# USB_FTDI.net
KiCad netlist of a schematic drawn in EAGLE
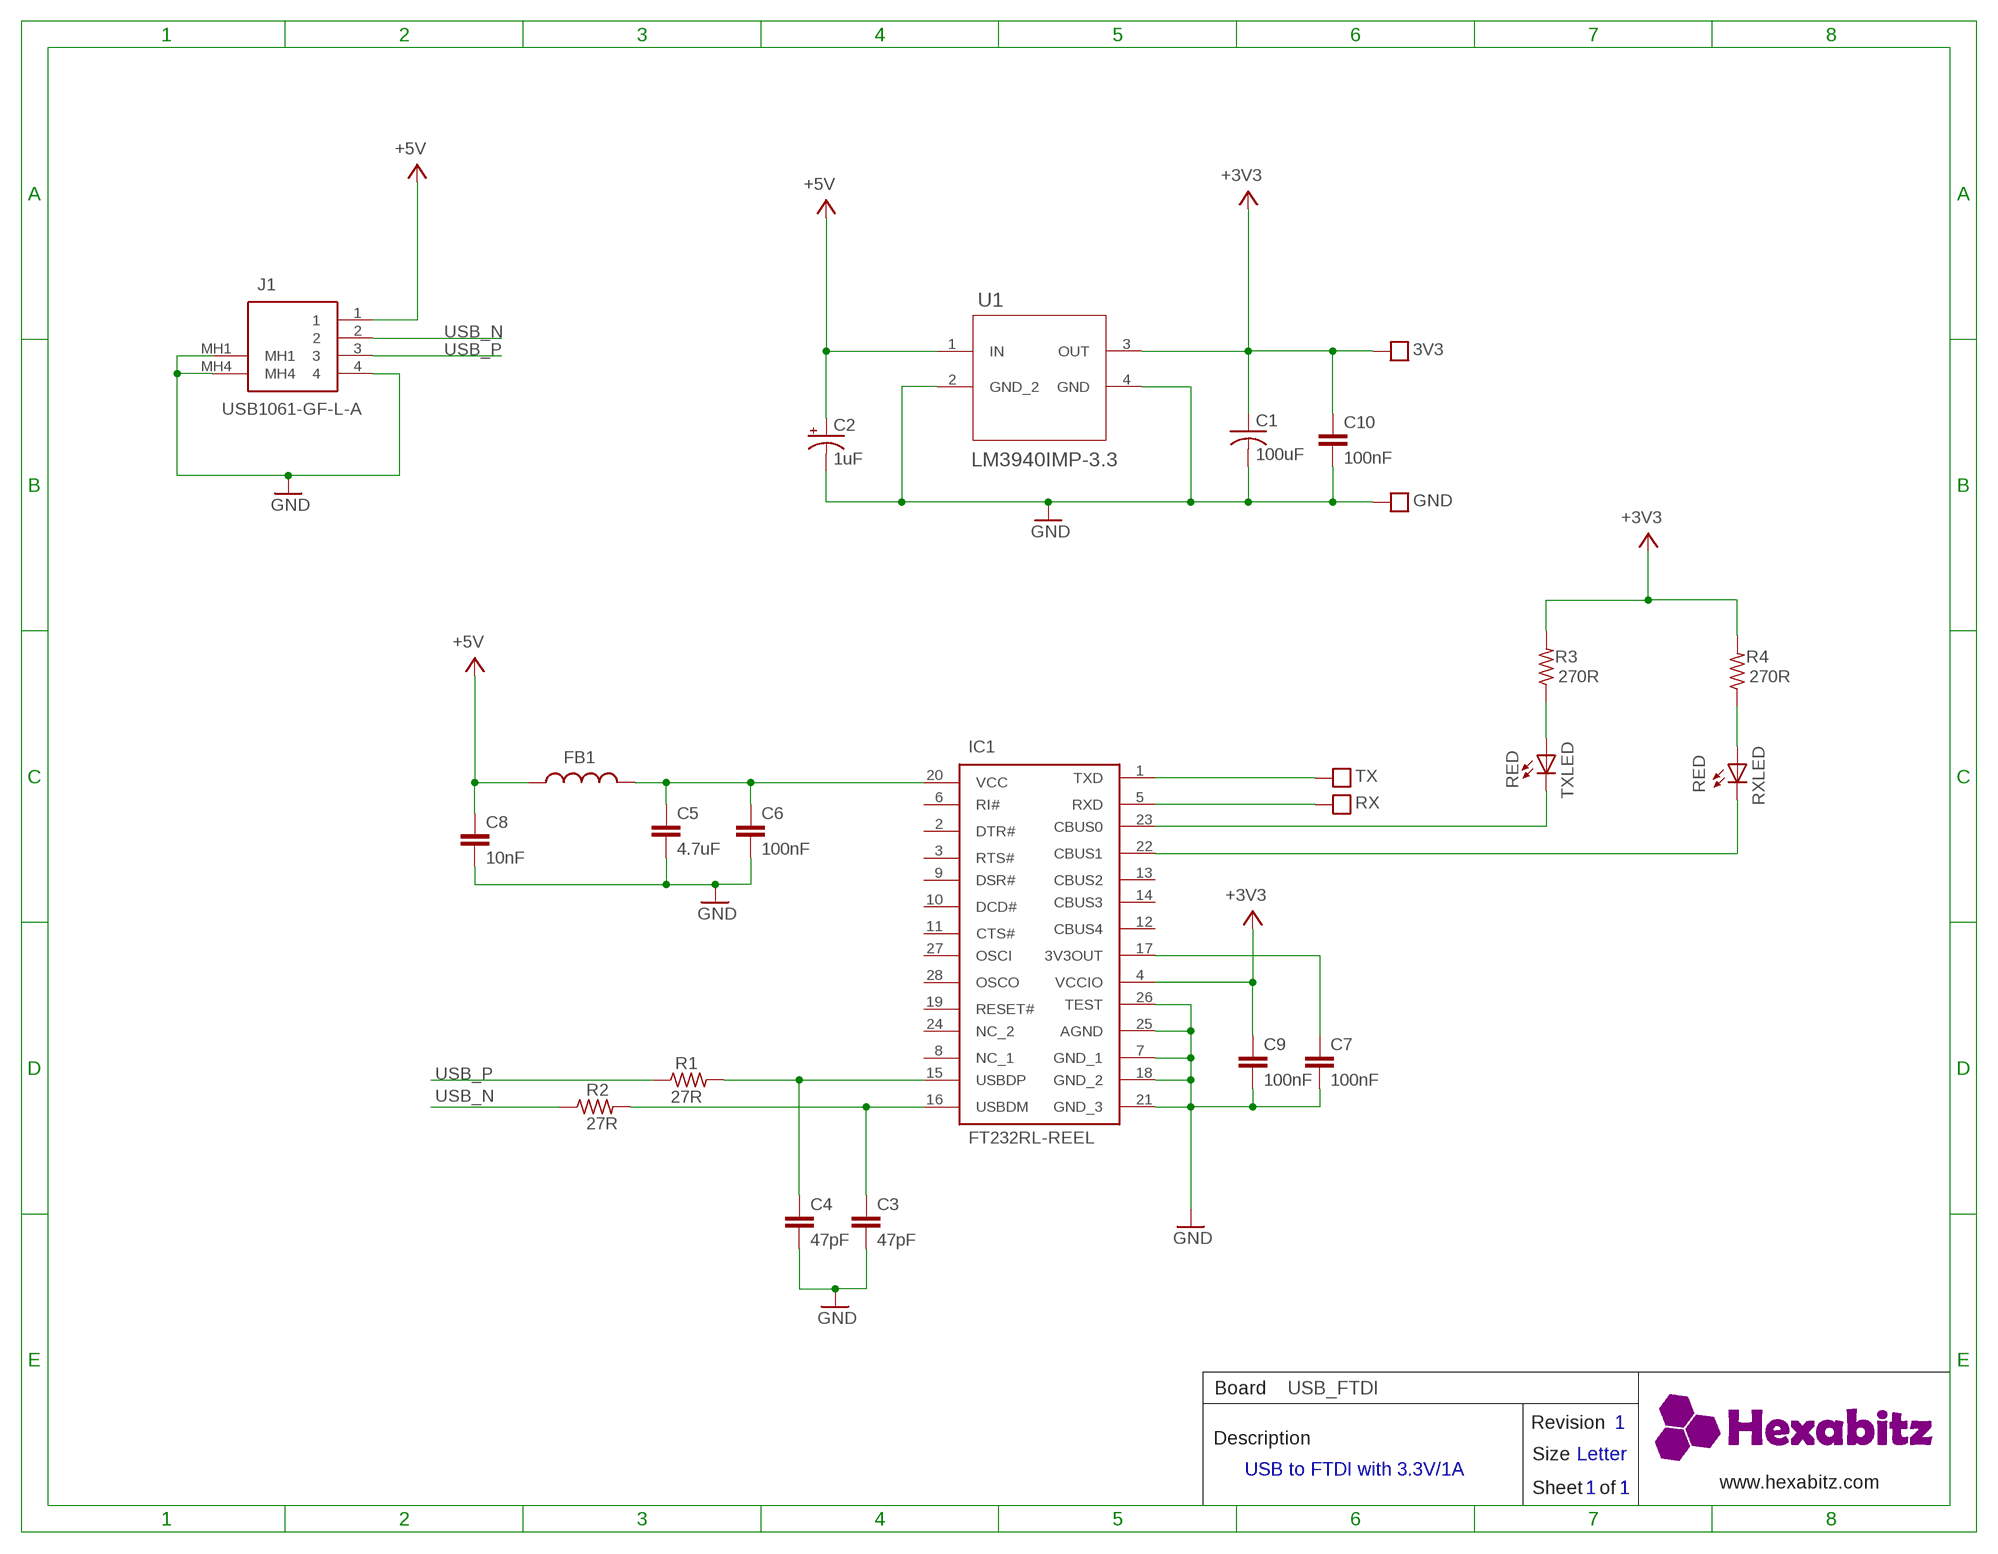
[diagram p0: schematic, sheet 1]

(export (version "E")
  (design (tool "Eeschema 10.0.6"))
  (components
    (comp (ref "3V3")
      (value "PAD5")
      (footprint "eagle-import:PAD5")
      (libsource (lib "eagle-import") (part "PAD5"))
    )
    (comp (ref "C1")
      (value "100uF")
      (footprint "eagle-import:C-1210")
      (libsource (lib "eagle-import") (part "C-1210"))
    )
    (comp (ref "C2")
      (value "1uF")
      (footprint "eagle-import:C-0805-POL")
      (libsource (lib "eagle-import") (part "C-0805-POL"))
    )
    (comp (ref "C3")
      (value "47pF")
      (footprint "eagle-import:C-0603")
      (libsource (lib "eagle-import") (part "C-0603"))
    )
    (comp (ref "C4")
      (value "47pF")
      (footprint "eagle-import:C-0603")
      (libsource (lib "eagle-import") (part "C-0603"))
    )
    (comp (ref "C5")
      (value "4.7uF")
      (footprint "eagle-import:C-0805")
      (libsource (lib "eagle-import") (part "C-0805"))
    )
    (comp (ref "C6")
      (value "100nF")
      (footprint "eagle-import:C-0603")
      (libsource (lib "eagle-import") (part "C-0603"))
    )
    (comp (ref "C7")
      (value "100nF")
      (footprint "eagle-import:C-0603")
      (libsource (lib "eagle-import") (part "C-0603"))
    )
    (comp (ref "C8")
      (value "10nF")
      (footprint "eagle-import:C-0603")
      (libsource (lib "eagle-import") (part "C-0603"))
    )
    (comp (ref "C9")
      (value "100nF")
      (footprint "eagle-import:C-0603")
      (libsource (lib "eagle-import") (part "C-0603"))
    )
    (comp (ref "C10")
      (value "100nF")
      (footprint "eagle-import:C-0603")
      (libsource (lib "eagle-import") (part "C-0603"))
    )
    (comp (ref "FB1")
      (value "FB-0603")
      (footprint "eagle-import:FB-0603")
      (libsource (lib "eagle-import") (part "FB-0603"))
    )
    (comp (ref "GND")
      (value "PAD5")
      (footprint "eagle-import:PAD5")
      (libsource (lib "eagle-import") (part "PAD5"))
    )
    (comp (ref "IC1")
      (value "FT232RL-REEL")
      (footprint "eagle-import:SOP65P778X200-28N")
      (fields (field (name "MOUSER_PART_NUMBER") "895-FT232RL"))
      (libsource (lib "eagle-import") (part "FT232RL-REEL"))
    )
    (comp (ref "J1")
      (value "USB1061-GF-L-A")
      (footprint "eagle-import:USB1061GFLA")
      (fields (field (name "MOUSER_PART_NUMBER") "640-USB1061-GF-L-A"))
      (libsource (lib "eagle-import") (part "USB1061-GF-L-A"))
    )
    (comp (ref "R1")
      (value "27R")
      (footprint "eagle-import:R-0603")
      (libsource (lib "eagle-import") (part "R-0603"))
    )
    (comp (ref "R2")
      (value "27R")
      (footprint "eagle-import:R-0603")
      (libsource (lib "eagle-import") (part "R-0603"))
    )
    (comp (ref "R3")
      (value "270R")
      (footprint "eagle-import:R-0603")
      (libsource (lib "eagle-import") (part "R-0603"))
    )
    (comp (ref "R4")
      (value "270R")
      (footprint "eagle-import:R-0603")
      (libsource (lib "eagle-import") (part "R-0603"))
    )
    (comp (ref "RX")
      (value "PAD5")
      (footprint "eagle-import:PAD5")
      (libsource (lib "eagle-import") (part "PAD5"))
    )
    (comp (ref "RXLED")
      (value "RED")
      (footprint "eagle-import:VLMS1300-GS08")
      (fields (field (name "MPN") "VLMS1300-GS08"))
      (libsource (lib "eagle-import") (part "VLMS1300-GS08"))
    )
    (comp (ref "TX")
      (value "PAD5")
      (footprint "eagle-import:PAD5")
      (libsource (lib "eagle-import") (part "PAD5"))
    )
    (comp (ref "TXLED")
      (value "RED")
      (footprint "eagle-import:VLMS1300-GS08")
      (fields (field (name "MPN") "VLMS1300-GS08"))
      (libsource (lib "eagle-import") (part "VLMS1300-GS08"))
    )
    (comp (ref "U1")
      (value "LM3940IMP-3.3")
      (footprint "eagle-import:SOT230P696X180-4N")
      (fields (field (name "MPN") "LM3940IMP-3.3/NOPB"))
      (libsource (lib "eagle-import") (part "LM3940IMP-3.3"))
    )
  )
  (nets
    (net (code "1") (name "+3V3") (class "Default")
      (node (ref "3V3") (pin "P$1") (pinfunction "P$1_P$1") (pintype "passive"))
      (node (ref "3V3") (pin "P$2") (pinfunction "P$1_P$2") (pintype "passive"))
      (node (ref "C1") (pin "1") (pinfunction "1_1") (pintype "passive"))
      (node (ref "C10") (pin "1") (pinfunction "1_1") (pintype "passive"))
      (node (ref "C9") (pin "1") (pinfunction "1_1") (pintype "passive"))
      (node (ref "IC1") (pin "4") (pinfunction "VCCIO_4") (pintype "bidirectional"))
      (node (ref "R3") (pin "2") (pinfunction "2_2") (pintype "passive"))
      (node (ref "R4") (pin "2") (pinfunction "2_2") (pintype "passive"))
      (node (ref "U1") (pin "3") (pinfunction "OUT_3") (pintype "output"))
    )
    (net (code "2") (name "+5V") (class "Default")
      (node (ref "C2") (pin "1") (pinfunction "+_1") (pintype "passive"))
      (node (ref "C8") (pin "1") (pinfunction "1_1") (pintype "passive"))
      (node (ref "FB1") (pin "1") (pinfunction "1_1") (pintype "passive"))
      (node (ref "J1") (pin "1") (pinfunction "1_1") (pintype "bidirectional"))
      (node (ref "U1") (pin "1") (pinfunction "IN_1") (pintype "power_in"))
    )
    (net (code "3") (name "/USB_N") (class "Default")
      (node (ref "J1") (pin "2") (pinfunction "2_2") (pintype "bidirectional"))
      (node (ref "R2") (pin "1") (pinfunction "1_1") (pintype "passive"))
    )
    (net (code "4") (name "/USB_P") (class "Default")
      (node (ref "J1") (pin "3") (pinfunction "3_3") (pintype "bidirectional"))
      (node (ref "R1") (pin "1") (pinfunction "1_1") (pintype "passive"))
    )
    (net (code "5") (name "GND") (class "Default")
      (node (ref "C1") (pin "2") (pinfunction "2_2") (pintype "passive"))
      (node (ref "C10") (pin "2") (pinfunction "2_2") (pintype "passive"))
      (node (ref "C2") (pin "2") (pinfunction "-_2") (pintype "passive"))
      (node (ref "C3") (pin "2") (pinfunction "2_2") (pintype "passive"))
      (node (ref "C4") (pin "2") (pinfunction "2_2") (pintype "passive"))
      (node (ref "C5") (pin "2") (pinfunction "2_2") (pintype "passive"))
      (node (ref "C6") (pin "2") (pinfunction "2_2") (pintype "passive"))
      (node (ref "C7") (pin "2") (pinfunction "2_2") (pintype "passive"))
      (node (ref "C8") (pin "2") (pinfunction "2_2") (pintype "passive"))
      (node (ref "C9") (pin "2") (pinfunction "2_2") (pintype "passive"))
      (node (ref "GND") (pin "P$1") (pinfunction "P$1_P$1") (pintype "passive"))
      (node (ref "GND") (pin "P$2") (pinfunction "P$1_P$2") (pintype "passive"))
      (node (ref "IC1") (pin "18") (pinfunction "GND_2_18") (pintype "bidirectional"))
      (node (ref "IC1") (pin "21") (pinfunction "GND_3_21") (pintype "bidirectional"))
      (node (ref "IC1") (pin "25") (pinfunction "AGND_25") (pintype "bidirectional"))
      (node (ref "IC1") (pin "26") (pinfunction "TEST_26") (pintype "bidirectional"))
      (node (ref "IC1") (pin "7") (pinfunction "GND_1_7") (pintype "bidirectional"))
      (node (ref "J1") (pin "4") (pinfunction "4_4") (pintype "bidirectional"))
      (node (ref "J1") (pin "MH1") (pinfunction "MH1_MH1") (pintype "bidirectional"))
      (node (ref "J1") (pin "MH4") (pinfunction "MH4_MH4") (pintype "bidirectional"))
      (node (ref "U1") (pin "2") (pinfunction "GND_2_2") (pintype "passive"))
      (node (ref "U1") (pin "4") (pinfunction "GND_4") (pintype "passive"))
    )
    (net (code "6") (name "Net-(IC1-3V3OUT)") (class "Default")
      (node (ref "C7") (pin "1") (pinfunction "1_1") (pintype "passive"))
      (node (ref "IC1") (pin "17") (pinfunction "3V3OUT_17") (pintype "bidirectional"))
    )
    (net (code "7") (name "Net-(IC1-CBUS0)") (class "Default")
      (node (ref "IC1") (pin "23") (pinfunction "CBUS0_23") (pintype "bidirectional"))
      (node (ref "TXLED") (pin "C") (pinfunction "C_C") (pintype "passive"))
    )
    (net (code "8") (name "Net-(IC1-CBUS1)") (class "Default")
      (node (ref "IC1") (pin "22") (pinfunction "CBUS1_22") (pintype "bidirectional"))
      (node (ref "RXLED") (pin "C") (pinfunction "C_C") (pintype "passive"))
    )
    (net (code "9") (name "Net-(IC1-RXD)") (class "Default")
      (node (ref "IC1") (pin "5") (pinfunction "RXD_5") (pintype "bidirectional"))
      (node (ref "RX") (pin "P$1") (pinfunction "P$1_P$1") (pintype "passive"))
      (node (ref "RX") (pin "P$2") (pinfunction "P$1_P$2") (pintype "passive"))
    )
    (net (code "10") (name "Net-(IC1-TXD)") (class "Default")
      (node (ref "IC1") (pin "1") (pinfunction "TXD_1") (pintype "bidirectional"))
      (node (ref "TX") (pin "P$1") (pinfunction "P$1_P$1") (pintype "passive"))
      (node (ref "TX") (pin "P$2") (pinfunction "P$1_P$2") (pintype "passive"))
    )
    (net (code "11") (name "Net-(IC1-USBDM)") (class "Default")
      (node (ref "C3") (pin "1") (pinfunction "1_1") (pintype "passive"))
      (node (ref "IC1") (pin "16") (pinfunction "USBDM_16") (pintype "bidirectional"))
      (node (ref "R2") (pin "2") (pinfunction "2_2") (pintype "passive"))
    )
    (net (code "12") (name "Net-(IC1-USBDP)") (class "Default")
      (node (ref "C4") (pin "1") (pinfunction "1_1") (pintype "passive"))
      (node (ref "IC1") (pin "15") (pinfunction "USBDP_15") (pintype "bidirectional"))
      (node (ref "R1") (pin "2") (pinfunction "2_2") (pintype "passive"))
    )
    (net (code "13") (name "Net-(IC1-VCC)") (class "Default")
      (node (ref "C5") (pin "1") (pinfunction "1_1") (pintype "passive"))
      (node (ref "C6") (pin "1") (pinfunction "1_1") (pintype "passive"))
      (node (ref "FB1") (pin "2") (pinfunction "2_2") (pintype "passive"))
      (node (ref "IC1") (pin "20") (pinfunction "VCC_20") (pintype "bidirectional"))
    )
    (net (code "14") (name "Net-(R3-Pad1)") (class "Default")
      (node (ref "R3") (pin "1") (pinfunction "1_1") (pintype "passive"))
      (node (ref "TXLED") (pin "A") (pinfunction "A_A") (pintype "passive"))
    )
    (net (code "15") (name "Net-(R4-Pad1)") (class "Default")
      (node (ref "R4") (pin "1") (pinfunction "1_1") (pintype "passive"))
      (node (ref "RXLED") (pin "A") (pinfunction "A_A") (pintype "passive"))
    )
    (net (code "16") (name "unconnected-(IC1-CBUS2-Pad13)") (class "Default")
      (node (ref "IC1") (pin "13") (pinfunction "CBUS2_13") (pintype "bidirectional"))
    )
    (net (code "17") (name "unconnected-(IC1-CBUS3-Pad14)") (class "Default")
      (node (ref "IC1") (pin "14") (pinfunction "CBUS3_14") (pintype "bidirectional"))
    )
    (net (code "18") (name "unconnected-(IC1-CBUS4-Pad12)") (class "Default")
      (node (ref "IC1") (pin "12") (pinfunction "CBUS4_12") (pintype "bidirectional"))
    )
    (net (code "19") (name "unconnected-(IC1-CTS#-Pad11)") (class "Default")
      (node (ref "IC1") (pin "11") (pinfunction "CTS#_11") (pintype "bidirectional"))
    )
    (net (code "20") (name "unconnected-(IC1-DCD#-Pad10)") (class "Default")
      (node (ref "IC1") (pin "10") (pinfunction "DCD#_10") (pintype "bidirectional"))
    )
    (net (code "21") (name "unconnected-(IC1-DSR#-Pad9)") (class "Default")
      (node (ref "IC1") (pin "9") (pinfunction "DSR#_9") (pintype "bidirectional"))
    )
    (net (code "22") (name "unconnected-(IC1-DTR#-Pad2)") (class "Default")
      (node (ref "IC1") (pin "2") (pinfunction "DTR#_2") (pintype "bidirectional"))
    )
    (net (code "23") (name "unconnected-(IC1-NC_1-Pad8)") (class "Default")
      (node (ref "IC1") (pin "8") (pinfunction "NC_1_8") (pintype "bidirectional"))
    )
    (net (code "24") (name "unconnected-(IC1-NC_2-Pad24)") (class "Default")
      (node (ref "IC1") (pin "24") (pinfunction "NC_2_24") (pintype "bidirectional"))
    )
    (net (code "25") (name "unconnected-(IC1-OSCI-Pad27)") (class "Default")
      (node (ref "IC1") (pin "27") (pinfunction "OSCI_27") (pintype "bidirectional"))
    )
    (net (code "26") (name "unconnected-(IC1-OSCO-Pad28)") (class "Default")
      (node (ref "IC1") (pin "28") (pinfunction "OSCO_28") (pintype "bidirectional"))
    )
    (net (code "27") (name "unconnected-(IC1-RESET#-Pad19)") (class "Default")
      (node (ref "IC1") (pin "19") (pinfunction "RESET#_19") (pintype "bidirectional"))
    )
    (net (code "28") (name "unconnected-(IC1-RI#-Pad6)") (class "Default")
      (node (ref "IC1") (pin "6") (pinfunction "RI#_6") (pintype "bidirectional"))
    )
    (net (code "29") (name "unconnected-(IC1-RTS#-Pad3)") (class "Default")
      (node (ref "IC1") (pin "3") (pinfunction "RTS#_3") (pintype "bidirectional"))
    )
  )
)
